# BMS029B_Monitor.net
KiCad netlist of a schematic drawn in Altium Designer
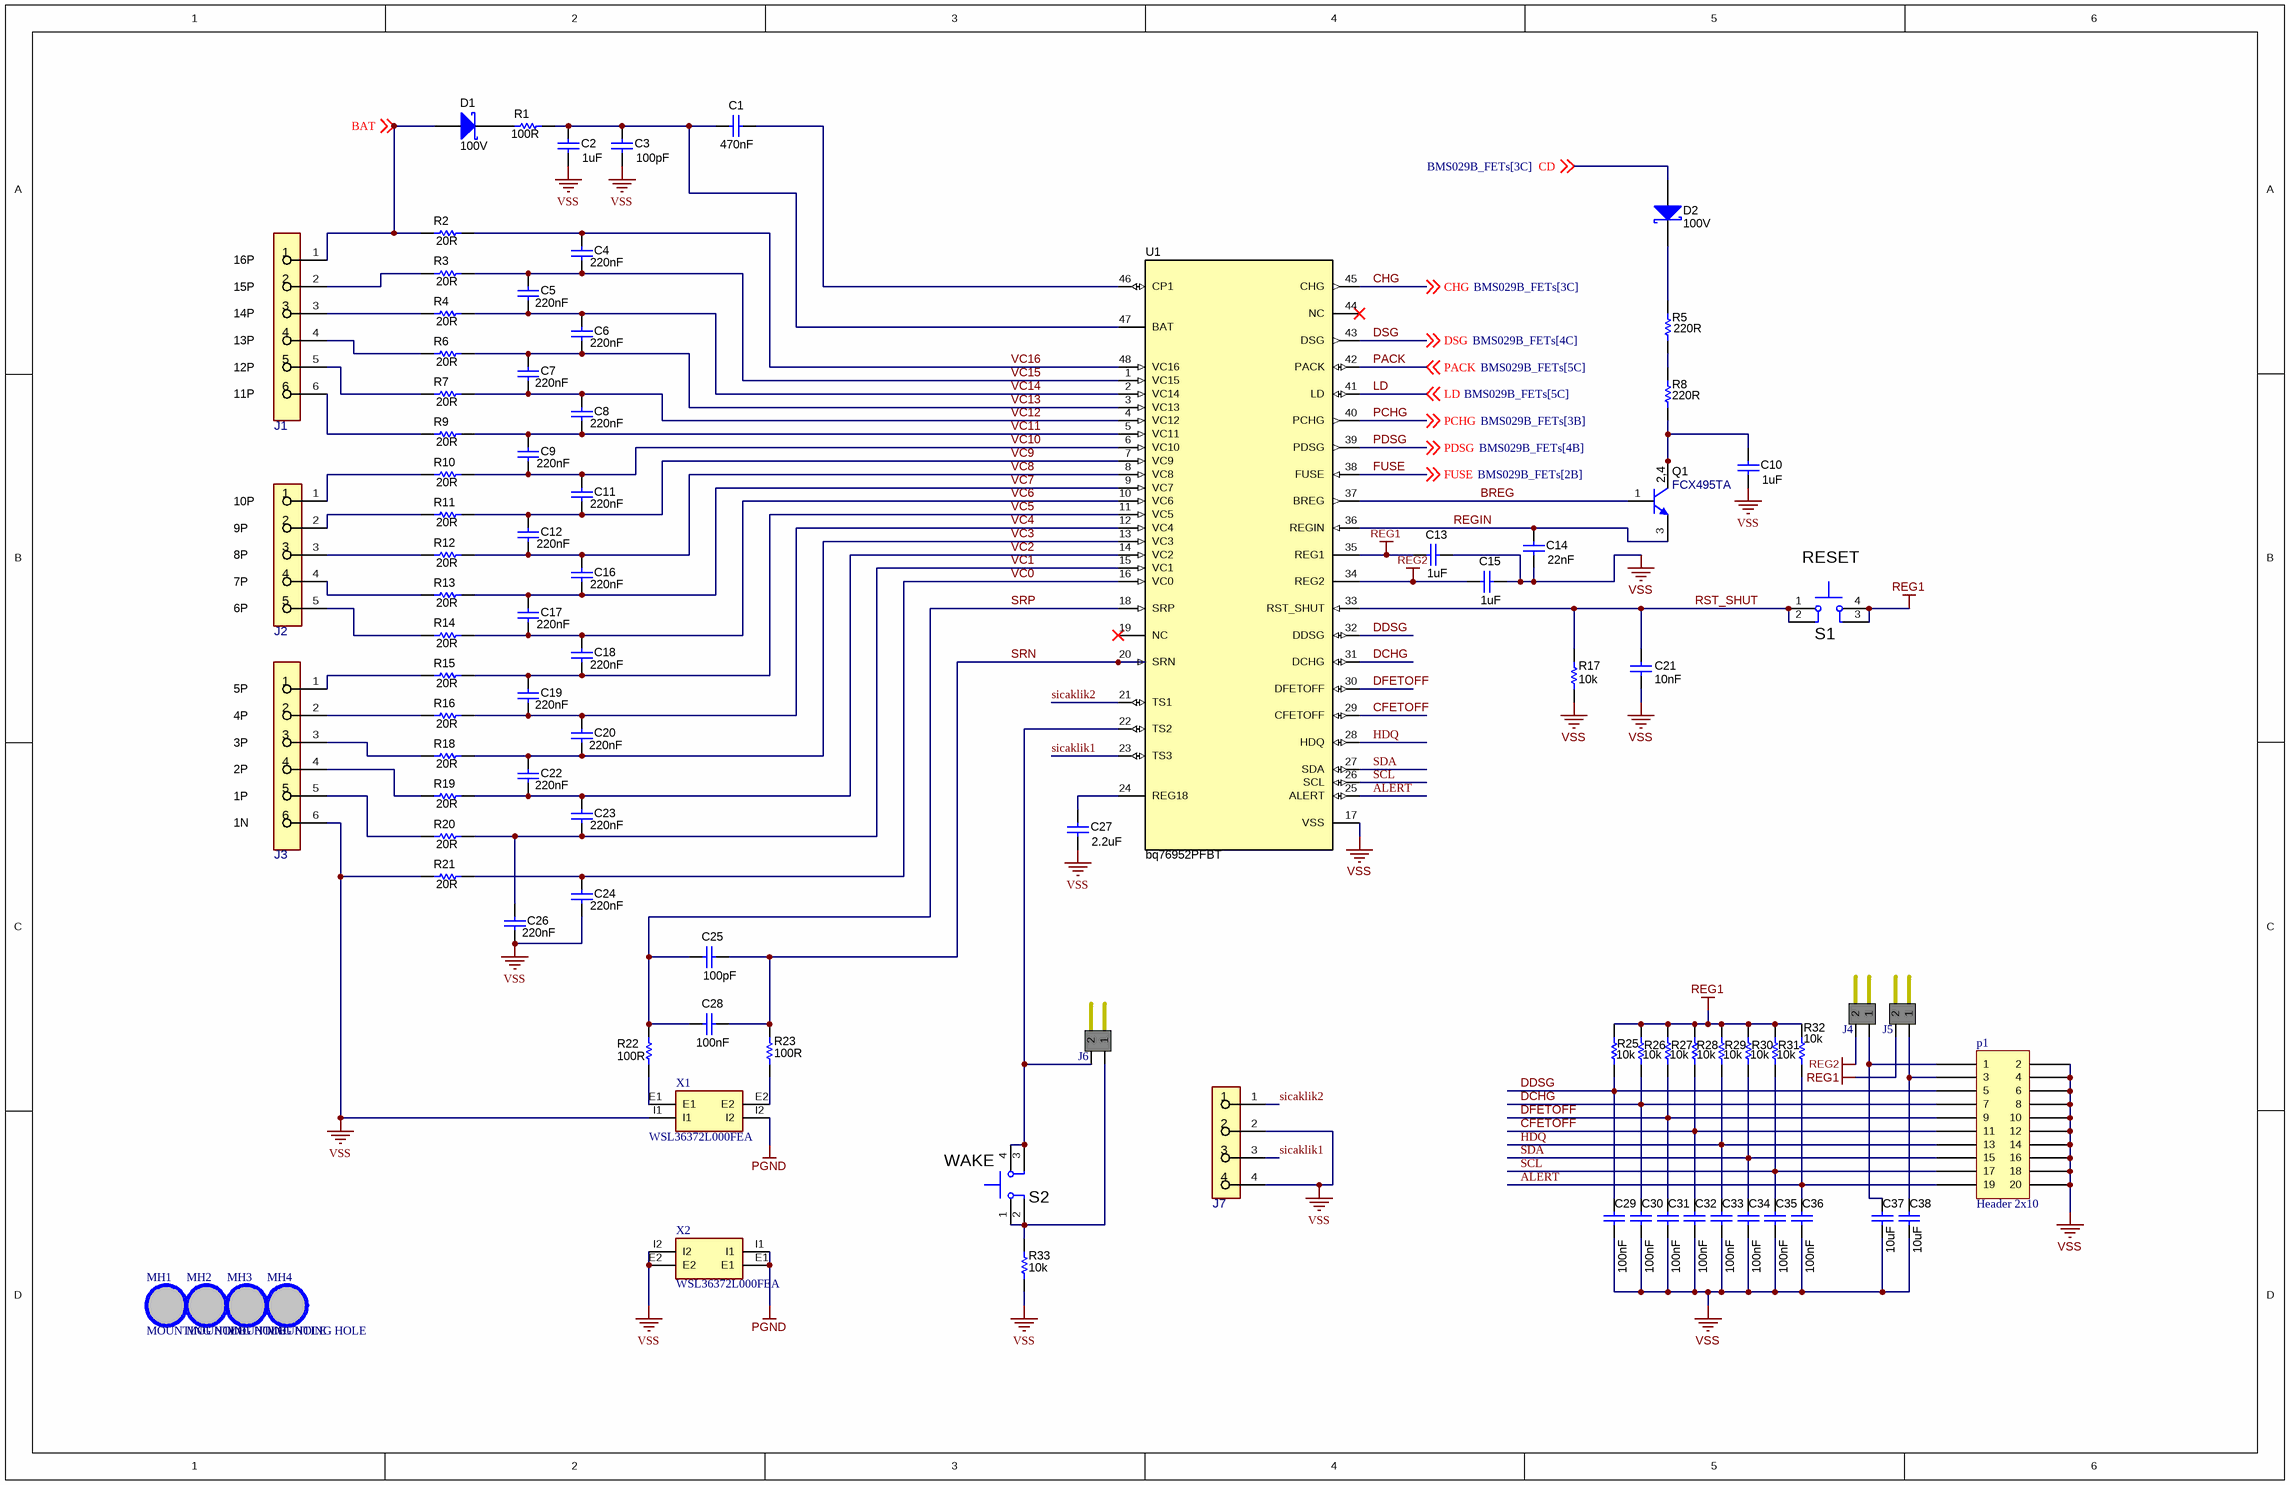
[diagram p0: BMS029B_Monitor.SchDoc]

(export (version "E")
  (design (tool "Eeschema 10.0.6"))
  (components
    (comp (ref "C1")
      (value "470nF")
      (footprint "0805_HV")
      (description "CAP, CERM, * uF, 100 V, +/- 10%, X7R, 0805")
      (fields
        (field (name "MANUFACTURER") "TDK")
        (field (name "PARTNUMBER") "C3216X7R2A105K160AA")
        (field (name "PUBLISHER") "Texas Instruments")
      )
      (libsource (lib "worklib") (part "Capacitor_0805"))
    )
    (comp (ref "C2")
      (value "1uF")
      (footprint "1206_180")
      (description "CAP, CERM, 1 uF, 100 V, +/- 10%, X7R, 1206")
      (fields
        (field (name "MANUFACTURER") "TDK")
        (field (name "PARTNUMBER") "C3216X7R2A105K160AA")
        (field (name "PUBLISHER") "Texas Instruments")
      )
      (libsource (lib "worklib") (part "Capacitor_1"))
    )
    (comp (ref "C3")
      (value "100pF")
      (footprint "0805_HV")
      (description "CAP, CERM, * uF, 100 V, +/- 10%, X7R, 0805")
      (fields
        (field (name "MANUFACTURER") "TDK")
        (field (name "PARTNUMBER") "C3216X7R2A105K160AA")
        (field (name "PUBLISHER") "Texas Instruments")
      )
      (libsource (lib "worklib") (part "Capacitor_0805"))
    )
    (comp (ref "C4")
      (value "220nF")
      (footprint "c0603")
      (description "CAP, CERM, 0.22 uF, 50 V, +/- 10%, X7R, 0603")
      (fields
        (field (name "MANUFACTURER") "TDK")
        (field (name "PARTNUMBER") "C1608X7R1H224K080AB")
        (field (name "PUBLISHER") "Texas Instruments")
      )
      (libsource (lib "worklib") (part "Capacitor"))
    )
    (comp (ref "C5")
      (value "220nF")
      (footprint "c0603")
      (description "CAP, CERM, 0.22 uF, 50 V, +/- 10%, X7R, 0603")
      (fields
        (field (name "MANUFACTURER") "TDK")
        (field (name "PARTNUMBER") "C1608X7R1H224K080AB")
        (field (name "PUBLISHER") "Texas Instruments")
      )
      (libsource (lib "worklib") (part "Capacitor"))
    )
    (comp (ref "C6")
      (value "220nF")
      (footprint "c0603")
      (description "CAP, CERM, 0.22 uF, 50 V, +/- 10%, X7R, 0603")
      (fields
        (field (name "MANUFACTURER") "TDK")
        (field (name "PARTNUMBER") "C1608X7R1H224K080AB")
        (field (name "PUBLISHER") "Texas Instruments")
      )
      (libsource (lib "worklib") (part "Capacitor"))
    )
    (comp (ref "C7")
      (value "220nF")
      (footprint "c0603")
      (description "CAP, CERM, 0.22 uF, 50 V, +/- 10%, X7R, 0603")
      (fields
        (field (name "MANUFACTURER") "TDK")
        (field (name "PARTNUMBER") "C1608X7R1H224K080AB")
        (field (name "PUBLISHER") "Texas Instruments")
      )
      (libsource (lib "worklib") (part "Capacitor"))
    )
    (comp (ref "C8")
      (value "220nF")
      (footprint "c0603")
      (description "CAP, CERM, 0.22 uF, 50 V, +/- 10%, X7R, 0603")
      (fields
        (field (name "MANUFACTURER") "TDK")
        (field (name "PARTNUMBER") "C1608X7R1H224K080AB")
        (field (name "PUBLISHER") "Texas Instruments")
      )
      (libsource (lib "worklib") (part "Capacitor"))
    )
    (comp (ref "C9")
      (value "220nF")
      (footprint "c0603")
      (description "CAP, CERM, 0.22 uF, 50 V, +/- 10%, X7R, 0603")
      (fields
        (field (name "MANUFACTURER") "TDK")
        (field (name "PARTNUMBER") "C1608X7R1H224K080AB")
        (field (name "PUBLISHER") "Texas Instruments")
      )
      (libsource (lib "worklib") (part "Capacitor"))
    )
    (comp (ref "C10")
      (value "1uF")
      (footprint "1206_180")
      (description "CAP, CERM, 1 uF, 100 V, +/- 10%, X7R, 1206")
      (fields
        (field (name "MANUFACTURER") "TDK")
        (field (name "PARTNUMBER") "C3216X7R2A105K160AA")
        (field (name "PUBLISHER") "Texas Instruments")
      )
      (libsource (lib "worklib") (part "Capacitor_1"))
    )
    (comp (ref "C11")
      (value "220nF")
      (footprint "c0603")
      (description "CAP, CERM, 0.22 uF, 50 V, +/- 10%, X7R, 0603")
      (fields
        (field (name "MANUFACTURER") "TDK")
        (field (name "PARTNUMBER") "C1608X7R1H224K080AB")
        (field (name "PUBLISHER") "Texas Instruments")
      )
      (libsource (lib "worklib") (part "Capacitor"))
    )
    (comp (ref "C12")
      (value "220nF")
      (footprint "c0603")
      (description "CAP, CERM, 0.22 uF, 50 V, +/- 10%, X7R, 0603")
      (fields
        (field (name "MANUFACTURER") "TDK")
        (field (name "PARTNUMBER") "C1608X7R1H224K080AB")
        (field (name "PUBLISHER") "Texas Instruments")
      )
      (libsource (lib "worklib") (part "Capacitor"))
    )
    (comp (ref "C13")
      (value "1uF")
      (footprint "0805_HV")
      (description "CAP, CERM, * uF, 100 V, +/- 10%, X7R, 0805")
      (fields
        (field (name "MANUFACTURER") "TDK")
        (field (name "PARTNUMBER") "C3216X7R2A105K160AA")
        (field (name "PUBLISHER") "Texas Instruments")
      )
      (libsource (lib "worklib") (part "Capacitor_0805"))
    )
    (comp (ref "C14")
      (value "22nF")
      (footprint "c0603")
      (description "CAP, CERM, 0.22 uF, 50 V, +/- 10%, X7R, 0603")
      (fields
        (field (name "MANUFACTURER") "TDK")
        (field (name "PARTNUMBER") "C1608X7R1H224K080AB")
        (field (name "PUBLISHER") "Texas Instruments")
      )
      (libsource (lib "worklib") (part "Capacitor"))
    )
    (comp (ref "C15")
      (value "1uF")
      (footprint "0805_HV")
      (description "CAP, CERM, * uF, 100 V, +/- 10%, X7R, 0805")
      (fields
        (field (name "MANUFACTURER") "TDK")
        (field (name "PARTNUMBER") "C3216X7R2A105K160AA")
        (field (name "PUBLISHER") "Texas Instruments")
      )
      (libsource (lib "worklib") (part "Capacitor_0805"))
    )
    (comp (ref "C16")
      (value "220nF")
      (footprint "c0603")
      (description "CAP, CERM, 0.22 uF, 50 V, +/- 10%, X7R, 0603")
      (fields
        (field (name "MANUFACTURER") "TDK")
        (field (name "PARTNUMBER") "C1608X7R1H224K080AB")
        (field (name "PUBLISHER") "Texas Instruments")
      )
      (libsource (lib "worklib") (part "Capacitor"))
    )
    (comp (ref "C17")
      (value "220nF")
      (footprint "c0603")
      (description "CAP, CERM, 0.22 uF, 50 V, +/- 10%, X7R, 0603")
      (fields
        (field (name "MANUFACTURER") "TDK")
        (field (name "PARTNUMBER") "C1608X7R1H224K080AB")
        (field (name "PUBLISHER") "Texas Instruments")
      )
      (libsource (lib "worklib") (part "Capacitor"))
    )
    (comp (ref "C18")
      (value "220nF")
      (footprint "c0603")
      (description "CAP, CERM, 0.22 uF, 50 V, +/- 10%, X7R, 0603")
      (fields
        (field (name "MANUFACTURER") "TDK")
        (field (name "PARTNUMBER") "C1608X7R1H224K080AB")
        (field (name "PUBLISHER") "Texas Instruments")
      )
      (libsource (lib "worklib") (part "Capacitor"))
    )
    (comp (ref "C19")
      (value "220nF")
      (footprint "c0603")
      (description "CAP, CERM, 0.22 uF, 50 V, +/- 10%, X7R, 0603")
      (fields
        (field (name "MANUFACTURER") "TDK")
        (field (name "PARTNUMBER") "C1608X7R1H224K080AB")
        (field (name "PUBLISHER") "Texas Instruments")
      )
      (libsource (lib "worklib") (part "Capacitor"))
    )
    (comp (ref "C20")
      (value "220nF")
      (footprint "c0603")
      (description "CAP, CERM, 0.22 uF, 50 V, +/- 10%, X7R, 0603")
      (fields
        (field (name "MANUFACTURER") "TDK")
        (field (name "PARTNUMBER") "C1608X7R1H224K080AB")
        (field (name "PUBLISHER") "Texas Instruments")
      )
      (libsource (lib "worklib") (part "Capacitor"))
    )
    (comp (ref "C21")
      (value "10nF")
      (footprint "0805_HV")
      (description "CAP, CERM, * uF, 100 V, +/- 10%, X7R, 0805")
      (fields
        (field (name "MANUFACTURER") "TDK")
        (field (name "PARTNUMBER") "C3216X7R2A105K160AA")
        (field (name "PUBLISHER") "Texas Instruments")
      )
      (libsource (lib "worklib") (part "Capacitor_0805"))
    )
    (comp (ref "C22")
      (value "220nF")
      (footprint "c0603")
      (description "CAP, CERM, 0.22 uF, 50 V, +/- 10%, X7R, 0603")
      (fields
        (field (name "MANUFACTURER") "TDK")
        (field (name "PARTNUMBER") "C1608X7R1H224K080AB")
        (field (name "PUBLISHER") "Texas Instruments")
      )
      (libsource (lib "worklib") (part "Capacitor"))
    )
    (comp (ref "C23")
      (value "220nF")
      (footprint "c0603")
      (description "CAP, CERM, 0.22 uF, 50 V, +/- 10%, X7R, 0603")
      (fields
        (field (name "MANUFACTURER") "TDK")
        (field (name "PARTNUMBER") "C1608X7R1H224K080AB")
        (field (name "PUBLISHER") "Texas Instruments")
      )
      (libsource (lib "worklib") (part "Capacitor"))
    )
    (comp (ref "C24")
      (value "220nF")
      (footprint "c0603")
      (description "CAP, CERM, 0.22 uF, 50 V, +/- 10%, X7R, 0603")
      (fields
        (field (name "MANUFACTURER") "TDK")
        (field (name "PARTNUMBER") "C1608X7R1H224K080AB")
        (field (name "PUBLISHER") "Texas Instruments")
      )
      (libsource (lib "worklib") (part "Capacitor"))
    )
    (comp (ref "C25")
      (value "100pF")
      (footprint "c0603")
      (description "CAP, CERM, 0.22 uF, 50 V, +/- 10%, X7R, 0603")
      (fields
        (field (name "MANUFACTURER") "TDK")
        (field (name "PARTNUMBER") "C1608X7R1H224K080AB")
        (field (name "PUBLISHER") "Texas Instruments")
      )
      (libsource (lib "worklib") (part "Capacitor"))
    )
    (comp (ref "C26")
      (value "220nF")
      (footprint "c0603")
      (description "CAP, CERM, 0.22 uF, 50 V, +/- 10%, X7R, 0603")
      (fields
        (field (name "MANUFACTURER") "TDK")
        (field (name "PARTNUMBER") "C1608X7R1H224K080AB")
        (field (name "PUBLISHER") "Texas Instruments")
      )
      (libsource (lib "worklib") (part "Capacitor"))
    )
    (comp (ref "C27")
      (value "2.2uF")
      (footprint "0805_HV")
      (description "CAP, CERM, * uF, 100 V, +/- 10%, X7R, 0805")
      (fields
        (field (name "MANUFACTURER") "TDK")
        (field (name "PARTNUMBER") "C3216X7R2A105K160AA")
        (field (name "PUBLISHER") "Texas Instruments")
      )
      (libsource (lib "worklib") (part "Capacitor_0805"))
    )
    (comp (ref "C28")
      (value "100nF")
      (footprint "c0603")
      (description "CAP, CERM, 0.22 uF, 50 V, +/- 10%, X7R, 0603")
      (fields
        (field (name "MANUFACTURER") "TDK")
        (field (name "PARTNUMBER") "C1608X7R1H224K080AB")
        (field (name "PUBLISHER") "Texas Instruments")
      )
      (libsource (lib "worklib") (part "Capacitor"))
    )
    (comp (ref "C29")
      (value "100nF")
      (footprint "c0603")
      (description "CAP, CERM, 0.22 uF, 50 V, +/- 10%, X7R, 0603")
      (fields
        (field (name "MANUFACTURER") "TDK")
        (field (name "PARTNUMBER") "C1608X7R1H224K080AB")
        (field (name "PUBLISHER") "Texas Instruments")
      )
      (libsource (lib "worklib") (part "Capacitor"))
    )
    (comp (ref "C30")
      (value "100nF")
      (footprint "c0603")
      (description "CAP, CERM, 0.22 uF, 50 V, +/- 10%, X7R, 0603")
      (fields
        (field (name "MANUFACTURER") "TDK")
        (field (name "PARTNUMBER") "C1608X7R1H224K080AB")
        (field (name "PUBLISHER") "Texas Instruments")
      )
      (libsource (lib "worklib") (part "Capacitor"))
    )
    (comp (ref "C31")
      (value "100nF")
      (footprint "c0603")
      (description "CAP, CERM, 0.22 uF, 50 V, +/- 10%, X7R, 0603")
      (fields
        (field (name "MANUFACTURER") "TDK")
        (field (name "PARTNUMBER") "C1608X7R1H224K080AB")
        (field (name "PUBLISHER") "Texas Instruments")
      )
      (libsource (lib "worklib") (part "Capacitor"))
    )
    (comp (ref "C32")
      (value "100nF")
      (footprint "c0603")
      (description "CAP, CERM, 0.22 uF, 50 V, +/- 10%, X7R, 0603")
      (fields
        (field (name "MANUFACTURER") "TDK")
        (field (name "PARTNUMBER") "C1608X7R1H224K080AB")
        (field (name "PUBLISHER") "Texas Instruments")
      )
      (libsource (lib "worklib") (part "Capacitor"))
    )
    (comp (ref "C33")
      (value "100nF")
      (footprint "c0603")
      (description "CAP, CERM, 0.22 uF, 50 V, +/- 10%, X7R, 0603")
      (fields
        (field (name "MANUFACTURER") "TDK")
        (field (name "PARTNUMBER") "C1608X7R1H224K080AB")
        (field (name "PUBLISHER") "Texas Instruments")
      )
      (libsource (lib "worklib") (part "Capacitor"))
    )
    (comp (ref "C34")
      (value "100nF")
      (footprint "c0603")
      (description "CAP, CERM, 0.22 uF, 50 V, +/- 10%, X7R, 0603")
      (fields
        (field (name "MANUFACTURER") "TDK")
        (field (name "PARTNUMBER") "C1608X7R1H224K080AB")
        (field (name "PUBLISHER") "Texas Instruments")
      )
      (libsource (lib "worklib") (part "Capacitor"))
    )
    (comp (ref "C35")
      (value "100nF")
      (footprint "c0603")
      (description "CAP, CERM, 0.22 uF, 50 V, +/- 10%, X7R, 0603")
      (fields
        (field (name "MANUFACTURER") "TDK")
        (field (name "PARTNUMBER") "C1608X7R1H224K080AB")
        (field (name "PUBLISHER") "Texas Instruments")
      )
      (libsource (lib "worklib") (part "Capacitor"))
    )
    (comp (ref "C36")
      (value "100nF")
      (footprint "c0603")
      (description "CAP, CERM, 0.22 uF, 50 V, +/- 10%, X7R, 0603")
      (fields
        (field (name "MANUFACTURER") "TDK")
        (field (name "PARTNUMBER") "C1608X7R1H224K080AB")
        (field (name "PUBLISHER") "Texas Instruments")
      )
      (libsource (lib "worklib") (part "Capacitor"))
    )
    (comp (ref "C37")
      (value "10uF")
      (footprint "c0603")
      (description "CAP, CERM, 0.22 uF, 50 V, +/- 10%, X7R, 0603")
      (fields
        (field (name "MANUFACTURER") "TDK")
        (field (name "PARTNUMBER") "C1608X7R1H224K080AB")
        (field (name "PUBLISHER") "Texas Instruments")
      )
      (libsource (lib "worklib") (part "Capacitor"))
    )
    (comp (ref "C38")
      (value "10uF")
      (footprint "c0603")
      (description "CAP, CERM, 0.22 uF, 50 V, +/- 10%, X7R, 0603")
      (fields
        (field (name "MANUFACTURER") "TDK")
        (field (name "PARTNUMBER") "C1608X7R1H224K080AB")
        (field (name "PUBLISHER") "Texas Instruments")
      )
      (libsource (lib "worklib") (part "Capacitor"))
    )
    (comp (ref "D1")
      (value "100V")
      (footprint "SOD-123")
      (description "Diode, Schottky, 100 V, 0.15 A, SOD-123")
      (fields (field (name "MANUFACTURER") "Diodes Inc.") (field (name "PARTNUMBER") "BAT46W-7-F"))
      (libsource (lib "worklib") (part "DIODE_SCHOTTKY"))
    )
    (comp (ref "D2")
      (value "100V")
      (footprint "SOD-123")
      (description "Diode, Schottky, 100 V, 0.15 A, SOD-123")
      (fields (field (name "MANUFACTURER") "Diodes Inc.") (field (name "PARTNUMBER") "BAT46W-7-F"))
      (libsource (lib "worklib") (part "DIODE_SCHOTTKY"))
    )
    (comp (ref "J1")
      (value "6-Pin JST XH")
      (footprint "6-Pin JST XH - Right Angle Connector Pinheader")
      (description "6-Pin JST XH - Right Angle Connector Pinheader")
      (fields (field (name "MANUFACTURER") "On Shore Technology") (field (name "PARTNUMBER") "OSTTE060161"))
      (libsource (lib "worklib") (part "6-Pin JST XH"))
    )
    (comp (ref "J2")
      (value "5-Pin JST XH")
      (footprint "5-Pin JST XH - Right Angle Connector Pinheader")
      (description "5-Pin JST XH - Right Angle Connector Pinheader")
      (fields (field (name "MANUFACTURER") "On Shore Technology") (field (name "PARTNUMBER") "OSTTE060161"))
      (libsource (lib "worklib") (part "5-Pin JST XH"))
    )
    (comp (ref "J3")
      (value "6-Pin JST XH")
      (footprint "6-Pin JST XH - Right Angle Connector Pinheader")
      (description "6-Pin JST XH - Right Angle Connector Pinheader")
      (fields (field (name "MANUFACTURER") "On Shore Technology") (field (name "PARTNUMBER") "OSTTE060161"))
      (libsource (lib "worklib") (part "6-Pin JST XH"))
    )
    (comp (ref "J4")
      (value "Jumper")
      (footprint "2 pin header")
      (description "Jumper 2")
      (libsource (lib "worklib") (part "Jumper 2"))
    )
    (comp (ref "J5")
      (value "Jumper")
      (footprint "2 pin header")
      (description "Jumper 2")
      (libsource (lib "worklib") (part "Jumper 2"))
    )
    (comp (ref "J6")
      (value "Jumper")
      (footprint "2 pin header")
      (description "Jumper 2")
      (libsource (lib "worklib") (part "Jumper 2"))
    )
    (comp (ref "J7")
      (value "4-Pin JST XH")
      (footprint "4-Pin JST XH - Right Angle Connector Pinheader")
      (description "4-Pin JST XH - Right Angle Connector Pinheader")
      (fields (field (name "MANUFACTURER") "On Shore Technology") (field (name "PARTNUMBER") "OSTTE060161"))
      (libsource (lib "worklib") (part "4-Pin JST XH"))
    )
    (comp (ref "MH1")
      (value "MOUNTING HOLE")
      (footprint "MOUNT-HOLE-M3")
      (libsource (lib "worklib") (part "MOUNTING HOLE"))
    )
    (comp (ref "MH2")
      (value "MOUNTING HOLE")
      (footprint "MOUNT-HOLE-M3")
      (libsource (lib "worklib") (part "MOUNTING HOLE"))
    )
    (comp (ref "MH3")
      (value "MOUNTING HOLE")
      (footprint "MOUNT-HOLE-M3")
      (libsource (lib "worklib") (part "MOUNTING HOLE"))
    )
    (comp (ref "MH4")
      (value "MOUNTING HOLE")
      (footprint "MOUNT-HOLE-M3")
      (libsource (lib "worklib") (part "MOUNTING HOLE"))
    )
    (comp (ref "p1")
      (value "Header 2x10")
      (footprint "Header 2x10 male rightangle")
      (description "Header 2x10 0.254mm")
      (libsource (lib "worklib") (part "Header 2x10"))
    )
    (comp (ref "Q1")
      (value "FCX495TA")
      (footprint "SOT-89-3")
      (description "Transistor, NPN, 150 V, 1 A, AEC-Q101, SOT-89")
      (fields (field (name "MANUFACTURER") "Diodes Inc.") (field (name "PUBLISHER") "Texas Instruments"))
      (libsource (lib "worklib") (part "BJT_NPN_C24B1E3"))
    )
    (comp (ref "R1")
      (value "100R")
      (footprint "SMD 0805 res")
      (description "0.25 W, AEC-Q200 Grade 0, 0805")
      (fields (field (name "PARTNUMBER") "CRCW120620R0FKEA") (field (name "MANUFACTURER") "Vishay-Dale"))
      (libsource (lib "worklib") (part "Resistor_0805"))
    )
    (comp (ref "R2")
      (value "20R")
      (footprint "2512")
      (description "RES, 20.0, 1%, 0.25 W, AEC-Q200 Grade 0, 1206")
      (fields (field (name "PARTNUMBER") "CRCW120620R0FKEA") (field (name "MANUFACTURER") "Vishay-Dale"))
      (libsource (lib "worklib") (part "Resistor"))
    )
    (comp (ref "R3")
      (value "20R")
      (footprint "2512")
      (description "RES, 20.0, 1%, 0.25 W, AEC-Q200 Grade 0, 1206")
      (fields (field (name "PARTNUMBER") "CRCW120620R0FKEA") (field (name "MANUFACTURER") "Vishay-Dale"))
      (libsource (lib "worklib") (part "Resistor"))
    )
    (comp (ref "R4")
      (value "20R")
      (footprint "2512")
      (description "RES, 20.0, 1%, 0.25 W, AEC-Q200 Grade 0, 1206")
      (fields (field (name "PARTNUMBER") "CRCW120620R0FKEA") (field (name "MANUFACTURER") "Vishay-Dale"))
      (libsource (lib "worklib") (part "Resistor"))
    )
    (comp (ref "R5")
      (value "220R")
      (footprint "2512")
      (description "RES, 20.0, 1%, 0.25 W, AEC-Q200 Grade 0, 1206")
      (fields (field (name "MANUFACTURER") "Vishay-Dale") (field (name "PARTNUMBER") "CRCW120620R0FKEA"))
      (libsource (lib "worklib") (part "Resistor_2512"))
    )
    (comp (ref "R6")
      (value "20R")
      (footprint "2512")
      (description "RES, 20.0, 1%, 0.25 W, AEC-Q200 Grade 0, 1206")
      (fields (field (name "PARTNUMBER") "CRCW120620R0FKEA") (field (name "MANUFACTURER") "Vishay-Dale"))
      (libsource (lib "worklib") (part "Resistor"))
    )
    (comp (ref "R7")
      (value "20R")
      (footprint "2512")
      (description "RES, 20.0, 1%, 0.25 W, AEC-Q200 Grade 0, 1206")
      (fields (field (name "PARTNUMBER") "CRCW120620R0FKEA") (field (name "MANUFACTURER") "Vishay-Dale"))
      (libsource (lib "worklib") (part "Resistor"))
    )
    (comp (ref "R8")
      (value "220R")
      (footprint "2512")
      (description "RES, 20.0, 1%, 0.25 W, AEC-Q200 Grade 0, 1206")
      (fields (field (name "MANUFACTURER") "Vishay-Dale") (field (name "PARTNUMBER") "CRCW120620R0FKEA"))
      (libsource (lib "worklib") (part "Resistor_2512"))
    )
    (comp (ref "R9")
      (value "20R")
      (footprint "2512")
      (description "RES, 20.0, 1%, 0.25 W, AEC-Q200 Grade 0, 1206")
      (fields (field (name "PARTNUMBER") "CRCW120620R0FKEA") (field (name "MANUFACTURER") "Vishay-Dale"))
      (libsource (lib "worklib") (part "Resistor"))
    )
    (comp (ref "R10")
      (value "20R")
      (footprint "2512")
      (description "RES, 20.0, 1%, 0.25 W, AEC-Q200 Grade 0, 1206")
      (fields (field (name "PARTNUMBER") "CRCW120620R0FKEA") (field (name "MANUFACTURER") "Vishay-Dale"))
      (libsource (lib "worklib") (part "Resistor"))
    )
    (comp (ref "R11")
      (value "20R")
      (footprint "2512")
      (description "RES, 20.0, 1%, 0.25 W, AEC-Q200 Grade 0, 1206")
      (fields (field (name "PARTNUMBER") "CRCW120620R0FKEA") (field (name "MANUFACTURER") "Vishay-Dale"))
      (libsource (lib "worklib") (part "Resistor"))
    )
    (comp (ref "R12")
      (value "20R")
      (footprint "2512")
      (description "RES, 20.0, 1%, 0.25 W, AEC-Q200 Grade 0, 1206")
      (fields (field (name "PARTNUMBER") "CRCW120620R0FKEA") (field (name "MANUFACTURER") "Vishay-Dale"))
      (libsource (lib "worklib") (part "Resistor"))
    )
    (comp (ref "R13")
      (value "20R")
      (footprint "2512")
      (description "RES, 20.0, 1%, 0.25 W, AEC-Q200 Grade 0, 1206")
      (fields (field (name "PARTNUMBER") "CRCW120620R0FKEA") (field (name "MANUFACTURER") "Vishay-Dale"))
      (libsource (lib "worklib") (part "Resistor"))
    )
    (comp (ref "R14")
      (value "20R")
      (footprint "2512")
      (description "RES, 20.0, 1%, 0.25 W, AEC-Q200 Grade 0, 1206")
      (fields (field (name "PARTNUMBER") "CRCW120620R0FKEA") (field (name "MANUFACTURER") "Vishay-Dale"))
      (libsource (lib "worklib") (part "Resistor"))
    )
    (comp (ref "R15")
      (value "20R")
      (footprint "2512")
      (description "RES, 20.0, 1%, 0.25 W, AEC-Q200 Grade 0, 1206")
      (fields (field (name "PARTNUMBER") "CRCW120620R0FKEA") (field (name "MANUFACTURER") "Vishay-Dale"))
      (libsource (lib "worklib") (part "Resistor"))
    )
    (comp (ref "R16")
      (value "20R")
      (footprint "2512")
      (description "RES, 20.0, 1%, 0.25 W, AEC-Q200 Grade 0, 1206")
      (fields (field (name "PARTNUMBER") "CRCW120620R0FKEA") (field (name "MANUFACTURER") "Vishay-Dale"))
      (libsource (lib "worklib") (part "Resistor"))
    )
    (comp (ref "R17")
      (value "10k")
      (footprint "SMD 0805 res")
      (description "0.25 W, AEC-Q200 Grade 0, 0805")
      (fields (field (name "MANUFACTURER") "Vishay-Dale") (field (name "PARTNUMBER") "CRCW120620R0FKEA"))
      (libsource (lib "worklib") (part "Resistor_0805"))
    )
    (comp (ref "R18")
      (value "20R")
      (footprint "2512")
      (description "RES, 20.0, 1%, 0.25 W, AEC-Q200 Grade 0, 1206")
      (fields (field (name "PARTNUMBER") "CRCW120620R0FKEA") (field (name "MANUFACTURER") "Vishay-Dale"))
      (libsource (lib "worklib") (part "Resistor"))
    )
    (comp (ref "R19")
      (value "20R")
      (footprint "2512")
      (description "RES, 20.0, 1%, 0.25 W, AEC-Q200 Grade 0, 1206")
      (fields (field (name "PARTNUMBER") "CRCW120620R0FKEA") (field (name "MANUFACTURER") "Vishay-Dale"))
      (libsource (lib "worklib") (part "Resistor"))
    )
    (comp (ref "R20")
      (value "20R")
      (footprint "2512")
      (description "RES, 20.0, 1%, 0.25 W, AEC-Q200 Grade 0, 1206")
      (fields (field (name "PARTNUMBER") "CRCW120620R0FKEA") (field (name "MANUFACTURER") "Vishay-Dale"))
      (libsource (lib "worklib") (part "Resistor"))
    )
    (comp (ref "R21")
      (value "20R")
      (footprint "2512")
      (description "RES, 20.0, 1%, 0.25 W, AEC-Q200 Grade 0, 1206")
      (fields (field (name "PARTNUMBER") "CRCW120620R0FKEA") (field (name "MANUFACTURER") "Vishay-Dale"))
      (libsource (lib "worklib") (part "Resistor"))
    )
    (comp (ref "R22")
      (value "100R")
      (footprint "0603S")
      (description "RES, 100, 5%, 0.1 W, AEC-Q200 Grade 0, 0603")
      (fields
        (field (name "PARTNUMBER") "CRCW0603100RJNEA")
        (field (name "MANUFACTURER") "Vishay-Dale")
        (field (name "PUBLISHER") "Texas Instruments")
      )
      (libsource (lib "worklib") (part "Resistor_0603"))
    )
    (comp (ref "R23")
      (value "100R")
      (footprint "0603S")
      (description "RES, 100, 5%, 0.1 W, AEC-Q200 Grade 0, 0603")
      (fields
        (field (name "PARTNUMBER") "CRCW0603100RJNEA")
        (field (name "MANUFACTURER") "Vishay-Dale")
        (field (name "PUBLISHER") "Texas Instruments")
      )
      (libsource (lib "worklib") (part "Resistor_0603"))
    )
    (comp (ref "R25")
      (value "10k")
      (footprint "SMD 0805 res")
      (description "0.25 W, AEC-Q200 Grade 0, 0805")
      (fields (field (name "PARTNUMBER") "CRCW120620R0FKEA") (field (name "MANUFACTURER") "Vishay-Dale"))
      (libsource (lib "worklib") (part "Resistor_0805"))
    )
    (comp (ref "R26")
      (value "10k")
      (footprint "SMD 0805 res")
      (description "0.25 W, AEC-Q200 Grade 0, 0805")
      (fields (field (name "PARTNUMBER") "CRCW120620R0FKEA") (field (name "MANUFACTURER") "Vishay-Dale"))
      (libsource (lib "worklib") (part "Resistor_0805"))
    )
    (comp (ref "R27")
      (value "10k")
      (footprint "SMD 0805 res")
      (description "0.25 W, AEC-Q200 Grade 0, 0805")
      (fields (field (name "PARTNUMBER") "CRCW120620R0FKEA") (field (name "MANUFACTURER") "Vishay-Dale"))
      (libsource (lib "worklib") (part "Resistor_0805"))
    )
    (comp (ref "R28")
      (value "10k")
      (footprint "SMD 0805 res")
      (description "0.25 W, AEC-Q200 Grade 0, 0805")
      (fields (field (name "PARTNUMBER") "CRCW120620R0FKEA") (field (name "MANUFACTURER") "Vishay-Dale"))
      (libsource (lib "worklib") (part "Resistor_0805"))
    )
    (comp (ref "R29")
      (value "10k")
      (footprint "SMD 0805 res")
      (description "0.25 W, AEC-Q200 Grade 0, 0805")
      (fields (field (name "PARTNUMBER") "CRCW120620R0FKEA") (field (name "MANUFACTURER") "Vishay-Dale"))
      (libsource (lib "worklib") (part "Resistor_0805"))
    )
    (comp (ref "R30")
      (value "10k")
      (footprint "SMD 0805 res")
      (description "0.25 W, AEC-Q200 Grade 0, 0805")
      (fields (field (name "PARTNUMBER") "CRCW120620R0FKEA") (field (name "MANUFACTURER") "Vishay-Dale"))
      (libsource (lib "worklib") (part "Resistor_0805"))
    )
    (comp (ref "R31")
      (value "10k")
      (footprint "SMD 0805 res")
      (description "0.25 W, AEC-Q200 Grade 0, 0805")
      (fields (field (name "PARTNUMBER") "CRCW120620R0FKEA") (field (name "MANUFACTURER") "Vishay-Dale"))
      (libsource (lib "worklib") (part "Resistor_0805"))
    )
    (comp (ref "R32")
      (value "10k")
      (footprint "SMD 0805 res")
      (description "0.25 W, AEC-Q200 Grade 0, 0805")
      (fields (field (name "PARTNUMBER") "CRCW120620R0FKEA") (field (name "MANUFACTURER") "Vishay-Dale"))
      (libsource (lib "worklib") (part "Resistor_0805"))
    )
    (comp (ref "R33")
      (value "10k")
      (footprint "0603S")
      (description "RES, 100, 5%, 0.1 W, AEC-Q200 Grade 0, 0603")
      (fields
        (field (name "MANUFACTURER") "Vishay-Dale")
        (field (name "PARTNUMBER") "CRCW0603100RJNEA")
        (field (name "PUBLISHER") "Texas Instruments")
      )
      (libsource (lib "worklib") (part "Resistor_0603"))
    )
    (comp (ref "S1")
      (value "SW_KST221JLFS")
      (footprint "L-KLS7-TS3402-2-5")
      (description "Switch, Tactile, SPST-NO, SMT")
      (fields
        (field (name "PARTNUMBER") "KST221JLFS")
        (field (name "MANUFACTURER") "C&K Components")
        (field (name "SYMBOLCREATOR") "a0799628")
        (field (name "PUBLISHER") "Texas Instruments")
      )
      (libsource (lib "worklib") (part "SW_KST221JLFS"))
    )
    (comp (ref "S2")
      (value "SW_KST221JLFS")
      (footprint "L-KLS7-TS3402-2-5")
      (description "Switch, Tactile, SPST-NO, SMT")
      (fields
        (field (name "PARTNUMBER") "KST221JLFS")
        (field (name "MANUFACTURER") "C&K Components")
        (field (name "SYMBOLCREATOR") "a0799628")
        (field (name "PUBLISHER") "Texas Instruments")
      )
      (libsource (lib "worklib") (part "SW_KST221JLFS"))
    )
    (comp (ref "U1")
      (value "bq76952PFBT")
      (footprint "PFB0048A_N")
      (description "Multicell Battery Monitor and Protection Family, PFB0048A (TQFP-48)")
      (fields
        (field (name "ALTERNATE PARTNUMBER") "bq76952PFBR")
        (field (name "MANUFACTURER") "Texas Instruments")
        (field (name "PARTNUMBER") "bq76952PFBT")
      )
      (libsource (lib "worklib") (part "bq76952"))
    )
    (comp (ref "X1")
      (value "WSL36372L000FEA")
      (footprint "WSL36372L000FEA")
      (description "Res Metal Strip 3637 0.002 Ohm 1% 3W +/-75ppm/C Sulfur Resistant Pad SMD Automotive T/R")
      (fields (field (name "MOUSER PART NUMBER") "71-WSL36372L000FEA"))
      (libsource (lib "worklib") (part "WSL36372L000FEA"))
    )
    (comp (ref "X2")
      (value "WSL36372L000FEA")
      (footprint "WSL36372L000FEA")
      (description "Res Metal Strip 3637 0.002 Ohm 1% 3W +/-75ppm/C Sulfur Resistant Pad SMD Automotive T/R")
      (fields (field (name "MOUSER PART NUMBER") "71-WSL36372L000FEA"))
      (libsource (lib "") (part "WSL36372L000FEA_1"))
    )
  )
  (nets
    (net (code "1") (name "/ALERT") (class "Default")
      (node (ref "C36") (pin "1") (pinfunction "1_1") (pintype "passive"))
      (node (ref "R32") (pin "2") (pinfunction "2_2") (pintype "passive"))
      (node (ref "U1") (pin "25") (pinfunction "ALERT_25") (pintype "bidirectional"))
      (node (ref "p1") (pin "19") (pinfunction "19_19") (pintype "passive"))
    )
    (net (code "2") (name "/BREG") (class "Default")
      (node (ref "Q1") (pin "1") (pinfunction "B_1") (pintype "passive"))
      (node (ref "U1") (pin "37") (pinfunction "BREG_37") (pintype "output"))
    )
    (net (code "3") (name "/CFETOFF") (class "Default")
      (node (ref "C32") (pin "1") (pinfunction "1_1") (pintype "passive"))
      (node (ref "R28") (pin "1") (pinfunction "1_1") (pintype "passive"))
      (node (ref "U1") (pin "29") (pinfunction "CFETOFF_29") (pintype "bidirectional"))
      (node (ref "p1") (pin "11") (pinfunction "11_11") (pintype "passive"))
    )
    (net (code "4") (name "/DCHG") (class "Default")
      (node (ref "C30") (pin "1") (pinfunction "1_1") (pintype "passive"))
      (node (ref "R26") (pin "1") (pinfunction "1_1") (pintype "passive"))
      (node (ref "U1") (pin "31") (pinfunction "DCHG_31") (pintype "bidirectional"))
      (node (ref "p1") (pin "7") (pinfunction "7_7") (pintype "passive"))
    )
    (net (code "5") (name "/DDSG") (class "Default")
      (node (ref "C29") (pin "1") (pinfunction "1_1") (pintype "passive"))
      (node (ref "R25") (pin "1") (pinfunction "1_1") (pintype "passive"))
      (node (ref "U1") (pin "32") (pinfunction "DDSG_32") (pintype "bidirectional"))
      (node (ref "p1") (pin "5") (pinfunction "5_5") (pintype "passive"))
    )
    (net (code "6") (name "/DFETOFF") (class "Default")
      (node (ref "C31") (pin "1") (pinfunction "1_1") (pintype "passive"))
      (node (ref "R27") (pin "1") (pinfunction "1_1") (pintype "passive"))
      (node (ref "U1") (pin "30") (pinfunction "DFETOFF_30") (pintype "bidirectional"))
      (node (ref "p1") (pin "9") (pinfunction "9_9") (pintype "passive"))
    )
    (net (code "7") (name "/HDQ") (class "Default")
      (node (ref "C33") (pin "1") (pinfunction "1_1") (pintype "passive"))
      (node (ref "R29") (pin "1") (pinfunction "1_1") (pintype "passive"))
      (node (ref "U1") (pin "28") (pinfunction "HDQ_28") (pintype "bidirectional"))
      (node (ref "p1") (pin "13") (pinfunction "13_13") (pintype "passive"))
    )
    (net (code "8") (name "/REGIN") (class "Default")
      (node (ref "C14") (pin "2") (pinfunction "2_2") (pintype "passive"))
      (node (ref "Q1") (pin "3") (pinfunction "E_3") (pintype "passive"))
      (node (ref "U1") (pin "36") (pinfunction "REGIN_36") (pintype "input"))
    )
    (net (code "9") (name "/RST_SHUT") (class "Default")
      (node (ref "C21") (pin "1") (pinfunction "1_1") (pintype "passive"))
      (node (ref "R17") (pin "1") (pinfunction "1_1") (pintype "passive"))
      (node (ref "S1") (pin "1") (pinfunction "1_1") (pintype "passive"))
      (node (ref "S1") (pin "2") (pinfunction "2_2") (pintype "passive"))
      (node (ref "U1") (pin "33") (pinfunction "RST_SHUT_33") (pintype "input"))
    )
    (net (code "10") (name "/SCL") (class "Default")
      (node (ref "C35") (pin "1") (pinfunction "1_1") (pintype "passive"))
      (node (ref "R31") (pin "1") (pinfunction "1_1") (pintype "passive"))
      (node (ref "U1") (pin "26") (pinfunction "SCL_26") (pintype "bidirectional"))
      (node (ref "p1") (pin "17") (pinfunction "17_17") (pintype "passive"))
    )
    (net (code "11") (name "/SDA") (class "Default")
      (node (ref "C34") (pin "1") (pinfunction "1_1") (pintype "passive"))
      (node (ref "R30") (pin "1") (pinfunction "1_1") (pintype "passive"))
      (node (ref "U1") (pin "27") (pinfunction "SDA_27") (pintype "bidirectional"))
      (node (ref "p1") (pin "15") (pinfunction "15_15") (pintype "passive"))
    )
    (net (code "12") (name "/SRN") (class "Default")
      (node (ref "C25") (pin "1") (pinfunction "1_1") (pintype "passive"))
      (node (ref "C28") (pin "2") (pinfunction "2_2") (pintype "passive"))
      (node (ref "R23") (pin "1") (pinfunction "1_1") (pintype "passive"))
      (node (ref "U1") (pin "20") (pinfunction "SRN_20") (pintype "input"))
    )
    (net (code "13") (name "/SRP") (class "Default")
      (node (ref "C25") (pin "2") (pinfunction "2_2") (pintype "passive"))
      (node (ref "C28") (pin "1") (pinfunction "1_1") (pintype "passive"))
      (node (ref "R22") (pin "1") (pinfunction "1_1") (pintype "passive"))
      (node (ref "U1") (pin "18") (pinfunction "SRP_18") (pintype "input"))
    )
    (net (code "14") (name "/VC0") (class "Default")
      (node (ref "C24") (pin "1") (pinfunction "1_1") (pintype "passive"))
      (node (ref "R21") (pin "2") (pinfunction "2_2") (pintype "passive"))
      (node (ref "U1") (pin "16") (pinfunction "VC0_16") (pintype "input"))
    )
    (net (code "15") (name "/VC1") (class "Default")
      (node (ref "C23") (pin "2") (pinfunction "2_2") (pintype "passive"))
      (node (ref "C26") (pin "1") (pinfunction "1_1") (pintype "passive"))
      (node (ref "R20") (pin "2") (pinfunction "2_2") (pintype "passive"))
      (node (ref "U1") (pin "15") (pinfunction "VC1_15") (pintype "input"))
    )
    (net (code "16") (name "/VC2") (class "Default")
      (node (ref "C22") (pin "2") (pinfunction "2_2") (pintype "passive"))
      (node (ref "C23") (pin "1") (pinfunction "1_1") (pintype "passive"))
      (node (ref "R19") (pin "2") (pinfunction "2_2") (pintype "passive"))
      (node (ref "U1") (pin "14") (pinfunction "VC2_14") (pintype "input"))
    )
    (net (code "17") (name "/VC3") (class "Default")
      (node (ref "C20") (pin "2") (pinfunction "2_2") (pintype "passive"))
      (node (ref "C22") (pin "1") (pinfunction "1_1") (pintype "passive"))
      (node (ref "R18") (pin "2") (pinfunction "2_2") (pintype "passive"))
      (node (ref "U1") (pin "13") (pinfunction "VC3_13") (pintype "input"))
    )
    (net (code "18") (name "/VC4") (class "Default")
      (node (ref "C19") (pin "2") (pinfunction "2_2") (pintype "passive"))
      (node (ref "C20") (pin "1") (pinfunction "1_1") (pintype "passive"))
      (node (ref "R16") (pin "2") (pinfunction "2_2") (pintype "passive"))
      (node (ref "U1") (pin "12") (pinfunction "VC4_12") (pintype "input"))
    )
    (net (code "19") (name "/VC5") (class "Default")
      (node (ref "C18") (pin "2") (pinfunction "2_2") (pintype "passive"))
      (node (ref "C19") (pin "1") (pinfunction "1_1") (pintype "passive"))
      (node (ref "R15") (pin "2") (pinfunction "2_2") (pintype "passive"))
      (node (ref "U1") (pin "11") (pinfunction "VC5_11") (pintype "input"))
    )
    (net (code "20") (name "/VC6") (class "Default")
      (node (ref "C17") (pin "2") (pinfunction "2_2") (pintype "passive"))
      (node (ref "C18") (pin "1") (pinfunction "1_1") (pintype "passive"))
      (node (ref "R14") (pin "2") (pinfunction "2_2") (pintype "passive"))
      (node (ref "U1") (pin "10") (pinfunction "VC6_10") (pintype "input"))
    )
    (net (code "21") (name "/VC7") (class "Default")
      (node (ref "C16") (pin "2") (pinfunction "2_2") (pintype "passive"))
      (node (ref "C17") (pin "1") (pinfunction "1_1") (pintype "passive"))
      (node (ref "R13") (pin "2") (pinfunction "2_2") (pintype "passive"))
      (node (ref "U1") (pin "9") (pinfunction "VC7_9") (pintype "input"))
    )
    (net (code "22") (name "/VC8") (class "Default")
      (node (ref "C12") (pin "2") (pinfunction "2_2") (pintype "passive"))
      (node (ref "C16") (pin "1") (pinfunction "1_1") (pintype "passive"))
      (node (ref "R12") (pin "2") (pinfunction "2_2") (pintype "passive"))
      (node (ref "U1") (pin "8") (pinfunction "VC8_8") (pintype "input"))
    )
    (net (code "23") (name "/VC9") (class "Default")
      (node (ref "C11") (pin "2") (pinfunction "2_2") (pintype "passive"))
      (node (ref "C12") (pin "1") (pinfunction "1_1") (pintype "passive"))
      (node (ref "R11") (pin "2") (pinfunction "2_2") (pintype "passive"))
      (node (ref "U1") (pin "7") (pinfunction "VC9_7") (pintype "input"))
    )
    (net (code "24") (name "/VC10") (class "Default")
      (node (ref "C11") (pin "1") (pinfunction "1_1") (pintype "passive"))
      (node (ref "C9") (pin "2") (pinfunction "2_2") (pintype "passive"))
      (node (ref "R10") (pin "2") (pinfunction "2_2") (pintype "passive"))
      (node (ref "U1") (pin "6") (pinfunction "VC10_6") (pintype "input"))
    )
    (net (code "25") (name "/VC11") (class "Default")
      (node (ref "C8") (pin "2") (pinfunction "2_2") (pintype "passive"))
      (node (ref "C9") (pin "1") (pinfunction "1_1") (pintype "passive"))
      (node (ref "R9") (pin "2") (pinfunction "2_2") (pintype "passive"))
      (node (ref "U1") (pin "5") (pinfunction "VC11_5") (pintype "input"))
    )
    (net (code "26") (name "/VC12") (class "Default")
      (node (ref "C7") (pin "2") (pinfunction "2_2") (pintype "passive"))
      (node (ref "C8") (pin "1") (pinfunction "1_1") (pintype "passive"))
      (node (ref "R7") (pin "2") (pinfunction "2_2") (pintype "passive"))
      (node (ref "U1") (pin "4") (pinfunction "VC12_4") (pintype "input"))
    )
    (net (code "27") (name "/VC13") (class "Default")
      (node (ref "C6") (pin "2") (pinfunction "2_2") (pintype "passive"))
      (node (ref "C7") (pin "1") (pinfunction "1_1") (pintype "passive"))
      (node (ref "R6") (pin "2") (pinfunction "2_2") (pintype "passive"))
      (node (ref "U1") (pin "3") (pinfunction "VC13_3") (pintype "input"))
    )
    (net (code "28") (name "/VC14") (class "Default")
      (node (ref "C5") (pin "2") (pinfunction "2_2") (pintype "passive"))
      (node (ref "C6") (pin "1") (pinfunction "1_1") (pintype "passive"))
      (node (ref "R4") (pin "2") (pinfunction "2_2") (pintype "passive"))
      (node (ref "U1") (pin "2") (pinfunction "VC14_2") (pintype "input"))
    )
    (net (code "29") (name "/VC15") (class "Default")
      (node (ref "C4") (pin "2") (pinfunction "2_2") (pintype "passive"))
      (node (ref "C5") (pin "1") (pinfunction "1_1") (pintype "passive"))
      (node (ref "R3") (pin "2") (pinfunction "2_2") (pintype "passive"))
      (node (ref "U1") (pin "1") (pinfunction "VC15_1") (pintype "input"))
    )
    (net (code "30") (name "/VC16") (class "Default")
      (node (ref "C4") (pin "1") (pinfunction "1_1") (pintype "passive"))
      (node (ref "R2") (pin "2") (pinfunction "2_2") (pintype "passive"))
      (node (ref "U1") (pin "48") (pinfunction "VC16_48") (pintype "input"))
    )
    (net (code "31") (name "/sicaklik1") (class "Default")
      (node (ref "J7") (pin "3") (pinfunction "3_3") (pintype "passive"))
      (node (ref "U1") (pin "23") (pinfunction "TS3_23") (pintype "bidirectional"))
    )
    (net (code "32") (name "/sicaklik2") (class "Default")
      (node (ref "J7") (pin "1") (pinfunction "1_1") (pintype "passive"))
      (node (ref "U1") (pin "21") (pinfunction "TS1_21") (pintype "bidirectional"))
    )
    (net (code "33") (name "BAT") (class "Default")
      (node (ref "D1") (pin "2") (pinfunction "A_2") (pintype "passive"))
      (node (ref "J1") (pin "1") (pinfunction "1_1") (pintype "passive"))
      (node (ref "R2") (pin "1") (pinfunction "1_1") (pintype "passive"))
    )
    (net (code "34") (name "CD") (class "Default")
      (node (ref "D2") (pin "2") (pinfunction "A_2") (pintype "passive"))
    )
    (net (code "35") (name "CHG") (class "Default")
      (node (ref "U1") (pin "45") (pinfunction "CHG_45") (pintype "output"))
    )
    (net (code "36") (name "DSG") (class "Default")
      (node (ref "U1") (pin "43") (pinfunction "DSG_43") (pintype "output"))
    )
    (net (code "37") (name "FUSE") (class "Default")
      (node (ref "U1") (pin "38") (pinfunction "FUSE_38") (pintype "input"))
    )
    (net (code "38") (name "LD") (class "Default")
      (node (ref "U1") (pin "41") (pinfunction "LD_41") (pintype "bidirectional"))
    )
    (net (code "39") (name "Net-(C10-Pad1)") (class "Default")
      (node (ref "C10") (pin "1") (pinfunction "1_1") (pintype "passive"))
      (node (ref "Q1") (pin "2") (pinfunction "C_2") (pintype "passive"))
      (node (ref "Q1") (pin "4") (pinfunction "C_4") (pintype "passive"))
      (node (ref "R8") (pin "1") (pinfunction "1_1") (pintype "passive"))
    )
    (net (code "40") (name "Net-(C37-Pad1)") (class "Default")
      (node (ref "C37") (pin "1") (pinfunction "1_1") (pintype "passive"))
      (node (ref "J4") (pin "1") (pinfunction "1_1") (pintype "passive"))
      (node (ref "p1") (pin "1") (pinfunction "1_1") (pintype "passive"))
    )
    (net (code "41") (name "Net-(C38-Pad1)") (class "Default")
      (node (ref "C38") (pin "1") (pinfunction "1_1") (pintype "passive"))
      (node (ref "J5") (pin "1") (pinfunction "1_1") (pintype "passive"))
      (node (ref "p1") (pin "3") (pinfunction "3_3") (pintype "passive"))
    )
    (net (code "42") (name "Net-(D1-K)") (class "Default")
      (node (ref "D1") (pin "1") (pinfunction "K_1") (pintype "passive"))
      (node (ref "R1") (pin "1") (pinfunction "1_1") (pintype "passive"))
    )
    (net (code "43") (name "Net-(D2-K)") (class "Default")
      (node (ref "D2") (pin "1") (pinfunction "K_1") (pintype "passive"))
      (node (ref "R5") (pin "2") (pinfunction "2_2") (pintype "passive"))
    )
    (net (code "44") (name "Net-(J1-Pad2)") (class "Default")
      (node (ref "J1") (pin "2") (pinfunction "2_2") (pintype "passive"))
      (node (ref "R3") (pin "1") (pinfunction "1_1") (pintype "passive"))
    )
    (net (code "45") (name "Net-(J1-Pad3)") (class "Default")
      (node (ref "J1") (pin "3") (pinfunction "3_3") (pintype "passive"))
      (node (ref "R4") (pin "1") (pinfunction "1_1") (pintype "passive"))
    )
    (net (code "46") (name "Net-(J1-Pad4)") (class "Default")
      (node (ref "J1") (pin "4") (pinfunction "4_4") (pintype "passive"))
      (node (ref "R6") (pin "1") (pinfunction "1_1") (pintype "passive"))
    )
    (net (code "47") (name "Net-(J1-Pad5)") (class "Default")
      (node (ref "J1") (pin "5") (pinfunction "5_5") (pintype "passive"))
      (node (ref "R7") (pin "1") (pinfunction "1_1") (pintype "passive"))
    )
    (net (code "48") (name "Net-(J1-Pad6)") (class "Default")
      (node (ref "J1") (pin "6") (pinfunction "6_6") (pintype "passive"))
      (node (ref "R9") (pin "1") (pinfunction "1_1") (pintype "passive"))
    )
    (net (code "49") (name "Net-(J2-Pad1)") (class "Default")
      (node (ref "J2") (pin "1") (pinfunction "1_1") (pintype "passive"))
      (node (ref "R10") (pin "1") (pinfunction "1_1") (pintype "passive"))
    )
    (net (code "50") (name "Net-(J2-Pad2)") (class "Default")
      (node (ref "J2") (pin "2") (pinfunction "2_2") (pintype "passive"))
      (node (ref "R11") (pin "1") (pinfunction "1_1") (pintype "passive"))
    )
    (net (code "51") (name "Net-(J2-Pad3)") (class "Default")
      (node (ref "J2") (pin "3") (pinfunction "3_3") (pintype "passive"))
      (node (ref "R12") (pin "1") (pinfunction "1_1") (pintype "passive"))
    )
    (net (code "52") (name "Net-(J2-Pad4)") (class "Default")
      (node (ref "J2") (pin "4") (pinfunction "4_4") (pintype "passive"))
      (node (ref "R13") (pin "1") (pinfunction "1_1") (pintype "passive"))
    )
    (net (code "53") (name "Net-(J2-Pad5)") (class "Default")
      (node (ref "J2") (pin "5") (pinfunction "5_5") (pintype "passive"))
      (node (ref "R14") (pin "1") (pinfunction "1_1") (pintype "passive"))
    )
    (net (code "54") (name "Net-(J3-Pad1)") (class "Default")
      (node (ref "J3") (pin "1") (pinfunction "1_1") (pintype "passive"))
      (node (ref "R15") (pin "1") (pinfunction "1_1") (pintype "passive"))
    )
    (net (code "55") (name "Net-(J3-Pad2)") (class "Default")
      (node (ref "J3") (pin "2") (pinfunction "2_2") (pintype "passive"))
      (node (ref "R16") (pin "1") (pinfunction "1_1") (pintype "passive"))
    )
    (net (code "56") (name "Net-(J3-Pad3)") (class "Default")
      (node (ref "J3") (pin "3") (pinfunction "3_3") (pintype "passive"))
      (node (ref "R18") (pin "1") (pinfunction "1_1") (pintype "passive"))
    )
    (net (code "57") (name "Net-(J3-Pad4)") (class "Default")
      (node (ref "J3") (pin "4") (pinfunction "4_4") (pintype "passive"))
      (node (ref "R19") (pin "1") (pinfunction "1_1") (pintype "passive"))
    )
    (net (code "58") (name "Net-(J3-Pad5)") (class "Default")
      (node (ref "J3") (pin "5") (pinfunction "5_5") (pintype "passive"))
      (node (ref "R20") (pin "1") (pinfunction "1_1") (pintype "passive"))
    )
    (net (code "59") (name "Net-(J6-Pad1)") (class "Default")
      (node (ref "J6") (pin "1") (pinfunction "1_1") (pintype "passive"))
      (node (ref "R33") (pin "1") (pinfunction "1_1") (pintype "passive"))
      (node (ref "S2") (pin "1") (pinfunction "1_1") (pintype "passive"))
      (node (ref "S2") (pin "2") (pinfunction "2_2") (pintype "passive"))
    )
    (net (code "60") (name "Net-(R5-Pad1)") (class "Default")
      (node (ref "R5") (pin "1") (pinfunction "1_1") (pintype "passive"))
      (node (ref "R8") (pin "2") (pinfunction "2_2") (pintype "passive"))
    )
    (net (code "61") (name "Net-(R22-Pad2)") (class "Default")
      (node (ref "R22") (pin "2") (pinfunction "2_2") (pintype "passive"))
      (node (ref "X1") (pin "E1") (pinfunction "E1_E1") (pintype "passive"))
    )
    (net (code "62") (name "Net-(R23-Pad2)") (class "Default")
      (node (ref "R23") (pin "2") (pinfunction "2_2") (pintype "passive"))
      (node (ref "X1") (pin "E2") (pinfunction "E2_E2") (pintype "passive"))
    )
    (net (code "63") (name "Net-(U1-BAT)") (class "Default")
      (node (ref "C1") (pin "1") (pinfunction "1_1") (pintype "passive"))
      (node (ref "C2") (pin "1") (pinfunction "1_1") (pintype "passive"))
      (node (ref "C3") (pin "1") (pinfunction "1_1") (pintype "passive"))
      (node (ref "R1") (pin "2") (pinfunction "2_2") (pintype "passive"))
      (node (ref "U1") (pin "47") (pinfunction "BAT_47") (pintype "power_in"))
    )
    (net (code "64") (name "Net-(U1-CP1)") (class "Default")
      (node (ref "C1") (pin "2") (pinfunction "2_2") (pintype "passive"))
      (node (ref "U1") (pin "46") (pinfunction "CP1_46") (pintype "bidirectional"))
    )
    (net (code "65") (name "Net-(U1-REG18)") (class "Default")
      (node (ref "C27") (pin "2") (pinfunction "2_2") (pintype "passive"))
      (node (ref "U1") (pin "24") (pinfunction "REG18_24") (pintype "power_in"))
    )
    (net (code "66") (name "Net-(U1-TS2)") (class "Default")
      (node (ref "J6") (pin "2") (pinfunction "2_2") (pintype "passive"))
      (node (ref "S2") (pin "3") (pinfunction "3_3") (pintype "passive"))
      (node (ref "S2") (pin "4") (pinfunction "4_4") (pintype "passive"))
      (node (ref "U1") (pin "22") (pinfunction "TS2_22") (pintype "bidirectional"))
    )
    (net (code "67") (name "PACK") (class "Default")
      (node (ref "U1") (pin "42") (pinfunction "PACK_42") (pintype "bidirectional"))
    )
    (net (code "68") (name "PCHG") (class "Default")
      (node (ref "U1") (pin "40") (pinfunction "PCHG_40") (pintype "output"))
    )
    (net (code "69") (name "PDSG") (class "Default")
      (node (ref "U1") (pin "39") (pinfunction "PDSG_39") (pintype "output"))
    )
    (net (code "70") (name "PGND") (class "Default")
      (node (ref "X1") (pin "I2") (pinfunction "I2_I2") (pintype "passive"))
      (node (ref "X2") (pin "E1") (pinfunction "E1_E1") (pintype "passive"))
      (node (ref "X2") (pin "I1") (pinfunction "I1_I1") (pintype "passive"))
    )
    (net (code "71") (name "REG1") (class "Default")
      (node (ref "C13") (pin "2") (pinfunction "2_2") (pintype "passive"))
      (node (ref "J5") (pin "2") (pinfunction "2_2") (pintype "passive"))
      (node (ref "R25") (pin "2") (pinfunction "2_2") (pintype "passive"))
      (node (ref "R26") (pin "2") (pinfunction "2_2") (pintype "passive"))
      (node (ref "R27") (pin "2") (pinfunction "2_2") (pintype "passive"))
      (node (ref "R28") (pin "2") (pinfunction "2_2") (pintype "passive"))
      (node (ref "R29") (pin "2") (pinfunction "2_2") (pintype "passive"))
      (node (ref "R30") (pin "2") (pinfunction "2_2") (pintype "passive"))
      (node (ref "R31") (pin "2") (pinfunction "2_2") (pintype "passive"))
      (node (ref "R32") (pin "1") (pinfunction "1_1") (pintype "passive"))
      (node (ref "S1") (pin "3") (pinfunction "3_3") (pintype "passive"))
      (node (ref "S1") (pin "4") (pinfunction "4_4") (pintype "passive"))
      (node (ref "U1") (pin "35") (pinfunction "REG1_35") (pintype "power_in"))
    )
    (net (code "72") (name "REG2") (class "Default")
      (node (ref "C15") (pin "2") (pinfunction "2_2") (pintype "passive"))
      (node (ref "J4") (pin "2") (pinfunction "2_2") (pintype "passive"))
      (node (ref "U1") (pin "34") (pinfunction "REG2_34") (pintype "power_in"))
    )
    (net (code "73") (name "VSS") (class "Default")
      (node (ref "C10") (pin "2") (pinfunction "2_2") (pintype "passive"))
      (node (ref "C13") (pin "1") (pinfunction "1_1") (pintype "passive"))
      (node (ref "C14") (pin "1") (pinfunction "1_1") (pintype "passive"))
      (node (ref "C15") (pin "1") (pinfunction "1_1") (pintype "passive"))
      (node (ref "C2") (pin "2") (pinfunction "2_2") (pintype "passive"))
      (node (ref "C21") (pin "2") (pinfunction "2_2") (pintype "passive"))
      (node (ref "C24") (pin "2") (pinfunction "2_2") (pintype "passive"))
      (node (ref "C26") (pin "2") (pinfunction "2_2") (pintype "passive"))
      (node (ref "C27") (pin "1") (pinfunction "1_1") (pintype "passive"))
      (node (ref "C29") (pin "2") (pinfunction "2_2") (pintype "passive"))
      (node (ref "C3") (pin "2") (pinfunction "2_2") (pintype "passive"))
      (node (ref "C30") (pin "2") (pinfunction "2_2") (pintype "passive"))
      (node (ref "C31") (pin "2") (pinfunction "2_2") (pintype "passive"))
      (node (ref "C32") (pin "2") (pinfunction "2_2") (pintype "passive"))
      (node (ref "C33") (pin "2") (pinfunction "2_2") (pintype "passive"))
      (node (ref "C34") (pin "2") (pinfunction "2_2") (pintype "passive"))
      (node (ref "C35") (pin "2") (pinfunction "2_2") (pintype "passive"))
      (node (ref "C36") (pin "2") (pinfunction "2_2") (pintype "passive"))
      (node (ref "C37") (pin "2") (pinfunction "2_2") (pintype "passive"))
      (node (ref "C38") (pin "2") (pinfunction "2_2") (pintype "passive"))
      (node (ref "J3") (pin "6") (pinfunction "6_6") (pintype "passive"))
      (node (ref "J7") (pin "2") (pinfunction "2_2") (pintype "passive"))
      (node (ref "J7") (pin "4") (pinfunction "4_4") (pintype "passive"))
      (node (ref "R17") (pin "2") (pinfunction "2_2") (pintype "passive"))
      (node (ref "R21") (pin "1") (pinfunction "1_1") (pintype "passive"))
      (node (ref "R33") (pin "2") (pinfunction "2_2") (pintype "passive"))
      (node (ref "U1") (pin "17") (pinfunction "VSS_17") (pintype "power_in"))
      (node (ref "X1") (pin "I1") (pinfunction "I1_I1") (pintype "passive"))
      (node (ref "X2") (pin "E2") (pinfunction "E2_E2") (pintype "passive"))
      (node (ref "X2") (pin "I2") (pinfunction "I2_I2") (pintype "passive"))
      (node (ref "p1") (pin "10") (pinfunction "10_10") (pintype "passive"))
      (node (ref "p1") (pin "12") (pinfunction "12_12") (pintype "passive"))
      (node (ref "p1") (pin "14") (pinfunction "14_14") (pintype "passive"))
      (node (ref "p1") (pin "16") (pinfunction "16_16") (pintype "passive"))
      (node (ref "p1") (pin "18") (pinfunction "18_18") (pintype "passive"))
      (node (ref "p1") (pin "2") (pinfunction "2_2") (pintype "passive"))
      (node (ref "p1") (pin "20") (pinfunction "20_20") (pintype "passive"))
      (node (ref "p1") (pin "4") (pinfunction "4_4") (pintype "passive"))
      (node (ref "p1") (pin "6") (pinfunction "6_6") (pintype "passive"))
      (node (ref "p1") (pin "8") (pinfunction "8_8") (pintype "passive"))
    )
    (net (code "74") (name "unconnected-(U1-NC-Pad19)") (class "Default")
      (node (ref "U1") (pin "19") (pinfunction "NC_19") (pintype "passive+no_connect"))
    )
    (net (code "75") (name "unconnected-(U1-NC-Pad44)") (class "Default")
      (node (ref "U1") (pin "44") (pinfunction "NC_44") (pintype "passive+no_connect"))
    )
  )
)
